# isolated_powerSerial_v2.net
KiCad netlist of a schematic drawn in EAGLE
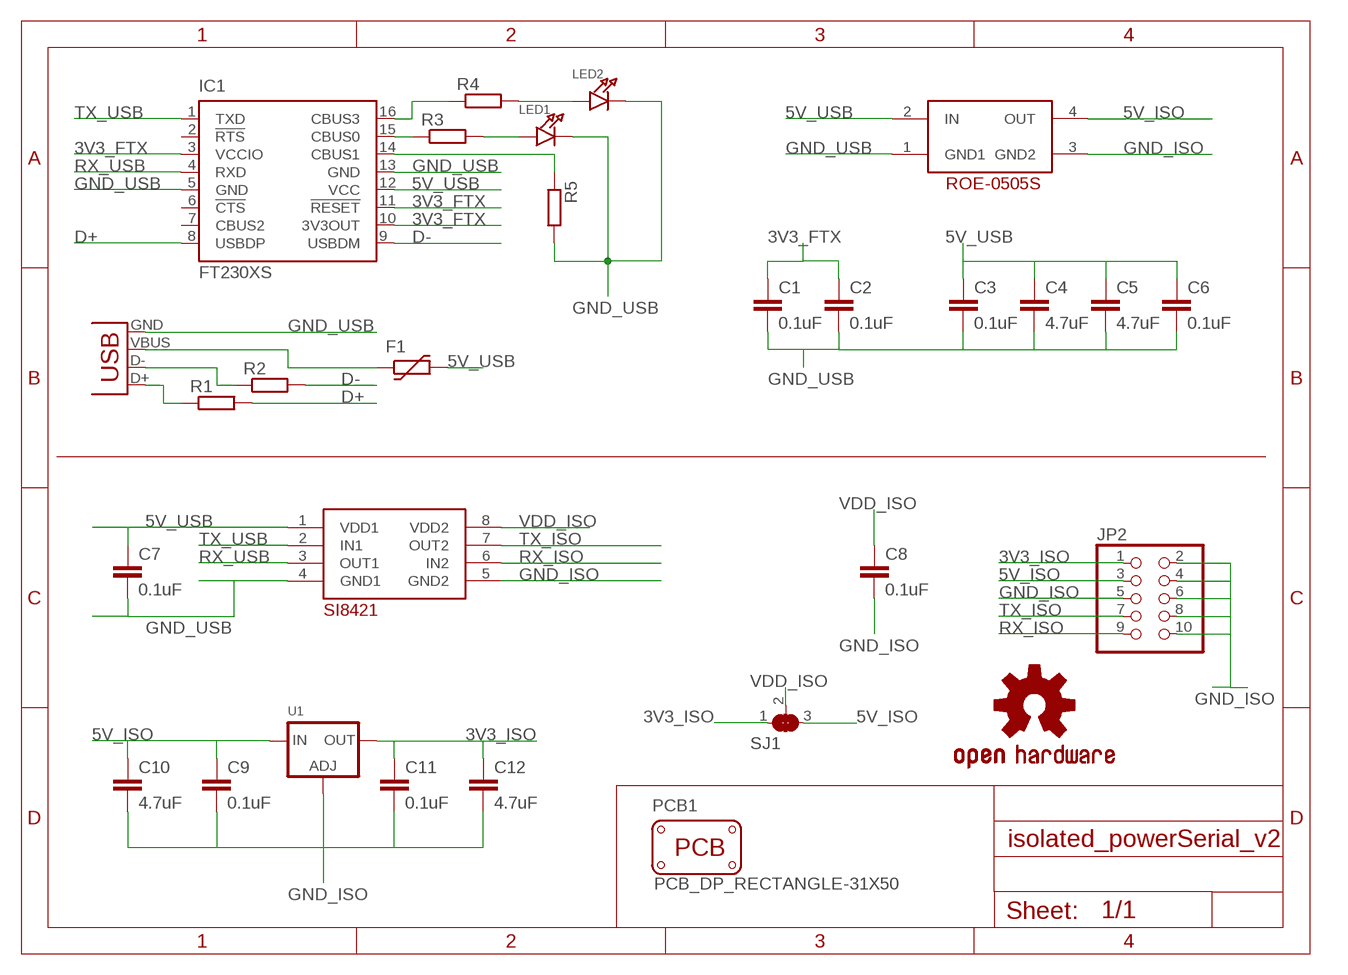
[diagram p0: schematic, sheet 1]

(export (version "E")
  (design (tool "Eeschema 10.0.6"))
  (components
    (comp (ref "C1")
      (value "0.1uF")
      (footprint "eagle-import:C0603")
      (libsource (lib "eagle-import") (part "C-EUC0603"))
    )
    (comp (ref "C2")
      (value "0.1uF")
      (footprint "eagle-import:C0603")
      (libsource (lib "eagle-import") (part "C-EUC0603"))
    )
    (comp (ref "C3")
      (value "0.1uF")
      (footprint "eagle-import:C0603")
      (libsource (lib "eagle-import") (part "C-EUC0603"))
    )
    (comp (ref "C4")
      (value "4.7uF")
      (footprint "eagle-import:C0603")
      (libsource (lib "eagle-import") (part "C-EUC0603"))
    )
    (comp (ref "C5")
      (value "4.7uF")
      (footprint "eagle-import:C0603")
      (libsource (lib "eagle-import") (part "C-EUC0603"))
    )
    (comp (ref "C6")
      (value "0.1uF")
      (footprint "eagle-import:C0603")
      (libsource (lib "eagle-import") (part "C-EUC0603"))
    )
    (comp (ref "C7")
      (value "0.1uF")
      (footprint "eagle-import:C0603")
      (libsource (lib "eagle-import") (part "C-EUC0603"))
    )
    (comp (ref "C8")
      (value "0.1uF")
      (footprint "eagle-import:C0603")
      (libsource (lib "eagle-import") (part "C-EUC0603"))
    )
    (comp (ref "C9")
      (value "0.1uF")
      (footprint "eagle-import:C0603")
      (libsource (lib "eagle-import") (part "C-EUC0603"))
    )
    (comp (ref "C10")
      (value "4.7uF")
      (footprint "eagle-import:C0603")
      (libsource (lib "eagle-import") (part "C-EUC0603"))
    )
    (comp (ref "C11")
      (value "0.1uF")
      (footprint "eagle-import:C0603")
      (libsource (lib "eagle-import") (part "C-EUC0603"))
    )
    (comp (ref "C12")
      (value "4.7uF")
      (footprint "eagle-import:C0603")
      (libsource (lib "eagle-import") (part "C-EUC0603"))
    )
    (comp (ref "F1")
      (value "FUSE_PTC-0805")
      (footprint "eagle-import:PTC0805")
      (libsource (lib "eagle-import") (part "FUSE_PTC-0805"))
    )
    (comp (ref "IC1")
      (value "FT230XS")
      (footprint "eagle-import:SSOP16")
      (libsource (lib "eagle-import") (part "FT230XS"))
    )
    (comp (ref "JP1")
      (value "USB-SMD-NS")
      (footprint "eagle-import:USB-MINIB-NOSTOP")
      (libsource (lib "eagle-import") (part "USB-SMD-NS"))
    )
    (comp (ref "JP2")
      (value "PINHD-2X5")
      (footprint "eagle-import:2X05")
      (libsource (lib "eagle-import") (part "PINHD-2X5"))
    )
    (comp (ref "LED1")
      (value "LED0805")
      (footprint "eagle-import:CHIPLED_0805")
      (libsource (lib "eagle-import") (part "LED0805"))
    )
    (comp (ref "LED2")
      (value "LED0805")
      (footprint "eagle-import:CHIPLED_0805")
      (libsource (lib "eagle-import") (part "LED0805"))
    )
    (comp (ref "LOGO1")
      (value "OSHW-LOGOS")
      (footprint "eagle-import:OSHW-LOGO-S")
      (libsource (lib "eagle-import") (part "OSHW-LOGOS"))
    )
    (comp (ref "PCB1")
      (value "PCB_DP_RECTANGLE-31X50")
      (footprint "eagle-import:DP5031_V1")
      (libsource (lib "eagle-import") (part "PCB_DP_RECTANGLE-31X50"))
    )
    (comp (ref "R1")
      (value "R-EU_R0603")
      (footprint "eagle-import:R0603")
      (libsource (lib "eagle-import") (part "R-EU_R0603"))
    )
    (comp (ref "R2")
      (value "R-EU_R0603")
      (footprint "eagle-import:R0603")
      (libsource (lib "eagle-import") (part "R-EU_R0603"))
    )
    (comp (ref "R3")
      (value "R-EU_R0603")
      (footprint "eagle-import:R0603")
      (libsource (lib "eagle-import") (part "R-EU_R0603"))
    )
    (comp (ref "R4")
      (value "R-EU_R0603")
      (footprint "eagle-import:R0603")
      (libsource (lib "eagle-import") (part "R-EU_R0603"))
    )
    (comp (ref "R5")
      (value "R-EU_R0603")
      (footprint "eagle-import:R0603")
      (libsource (lib "eagle-import") (part "R-EU_R0603"))
    )
    (comp (ref "SJ1")
      (value "SOLDERJUMPER_2WAY0603")
      (footprint "eagle-import:SOLDERJUMPER_2WAY_OPEN_0603")
      (libsource (lib "eagle-import") (part "SOLDERJUMPER_2WAY0603"))
    )
    (comp (ref "U$1")
      (value "IHSAN_RECOM_ROE-0505S")
      (footprint "eagle-import:IHSAN_ROE")
      (libsource (lib "eagle-import") (part "IHSAN_RECOM_ROE-0505S"))
    )
    (comp (ref "U$2")
      (value "IHSAN_SI8421")
      (footprint "eagle-import:SO08")
      (libsource (lib "eagle-import") (part "IHSAN_SI8421"))
    )
    (comp (ref "U1")
      (value "LM1117SOT223-REFLOW")
      (footprint "eagle-import:SOT223-R")
      (libsource (lib "eagle-import") (part "LM1117SOT223-REFLOW"))
    )
  )
  (nets
    (net (code "1") (name "/3V3_FTX") (class "Default")
      (node (ref "C1") (pin "1") (pinfunction "1_1") (pintype "passive"))
      (node (ref "C2") (pin "1") (pinfunction "1_1") (pintype "passive"))
      (node (ref "IC1") (pin "10") (pinfunction "3V3OUT_10") (pintype "output"))
      (node (ref "IC1") (pin "11") (pinfunction "~{RESET}_11") (pintype "input"))
      (node (ref "IC1") (pin "3") (pinfunction "VCCIO_3") (pintype "power_in"))
    )
    (net (code "2") (name "/3V3_ISO") (class "Default")
      (node (ref "C11") (pin "1") (pinfunction "1_1") (pintype "passive"))
      (node (ref "C12") (pin "1") (pinfunction "1_1") (pintype "passive"))
      (node (ref "JP2") (pin "1") (pinfunction "1_1") (pintype "passive"))
      (node (ref "SJ1") (pin "1") (pinfunction "1_1") (pintype "passive"))
      (node (ref "U1") (pin "2") (pinfunction "OUT_2") (pintype "passive"))
    )
    (net (code "3") (name "/5V_ISO") (class "Default")
      (node (ref "C10") (pin "1") (pinfunction "1_1") (pintype "passive"))
      (node (ref "C9") (pin "1") (pinfunction "1_1") (pintype "passive"))
      (node (ref "JP2") (pin "3") (pinfunction "3_3") (pintype "passive"))
      (node (ref "SJ1") (pin "3") (pinfunction "3_3") (pintype "passive"))
      (node (ref "U$1") (pin "4") (pinfunction "OUT_4") (pintype "bidirectional"))
      (node (ref "U1") (pin "3") (pinfunction "IN_3") (pintype "input"))
    )
    (net (code "4") (name "/5V_USB") (class "Default")
      (node (ref "C3") (pin "1") (pinfunction "1_1") (pintype "passive"))
      (node (ref "C4") (pin "1") (pinfunction "1_1") (pintype "passive"))
      (node (ref "C5") (pin "1") (pinfunction "1_1") (pintype "passive"))
      (node (ref "C6") (pin "1") (pinfunction "1_1") (pintype "passive"))
      (node (ref "C7") (pin "1") (pinfunction "1_1") (pintype "passive"))
      (node (ref "F1") (pin "2") (pinfunction "2_2") (pintype "passive"))
      (node (ref "IC1") (pin "12") (pinfunction "VCC_12") (pintype "power_in"))
      (node (ref "U$1") (pin "2") (pinfunction "IN_2") (pintype "bidirectional"))
      (node (ref "U$2") (pin "1") (pinfunction "VDD1_1") (pintype "bidirectional"))
    )
    (net (code "5") (name "/D+") (class "Default")
      (node (ref "IC1") (pin "8") (pinfunction "USBDP_8") (pintype "input"))
      (node (ref "R1") (pin "2") (pinfunction "2_2") (pintype "passive"))
    )
    (net (code "6") (name "/D-") (class "Default")
      (node (ref "IC1") (pin "9") (pinfunction "USBDM_9") (pintype "input"))
      (node (ref "R2") (pin "2") (pinfunction "2_2") (pintype "passive"))
    )
    (net (code "7") (name "/GND_ISO") (class "Default")
      (node (ref "C10") (pin "2") (pinfunction "2_2") (pintype "passive"))
      (node (ref "C11") (pin "2") (pinfunction "2_2") (pintype "passive"))
      (node (ref "C12") (pin "2") (pinfunction "2_2") (pintype "passive"))
      (node (ref "C8") (pin "2") (pinfunction "2_2") (pintype "passive"))
      (node (ref "C9") (pin "2") (pinfunction "2_2") (pintype "passive"))
      (node (ref "JP2") (pin "10") (pinfunction "10_10") (pintype "passive"))
      (node (ref "JP2") (pin "2") (pinfunction "2_2") (pintype "passive"))
      (node (ref "JP2") (pin "4") (pinfunction "4_4") (pintype "passive"))
      (node (ref "JP2") (pin "5") (pinfunction "5_5") (pintype "passive"))
      (node (ref "JP2") (pin "6") (pinfunction "6_6") (pintype "passive"))
      (node (ref "JP2") (pin "8") (pinfunction "8_8") (pintype "passive"))
      (node (ref "U$1") (pin "3") (pinfunction "GND2_3") (pintype "bidirectional"))
      (node (ref "U$2") (pin "5") (pinfunction "GND2_5") (pintype "bidirectional"))
      (node (ref "U1") (pin "1") (pinfunction "ADJ_1") (pintype "input"))
    )
    (net (code "8") (name "/GND_USB") (class "Default")
      (node (ref "C1") (pin "2") (pinfunction "2_2") (pintype "passive"))
      (node (ref "C2") (pin "2") (pinfunction "2_2") (pintype "passive"))
      (node (ref "C3") (pin "2") (pinfunction "2_2") (pintype "passive"))
      (node (ref "C4") (pin "2") (pinfunction "2_2") (pintype "passive"))
      (node (ref "C5") (pin "2") (pinfunction "2_2") (pintype "passive"))
      (node (ref "C6") (pin "2") (pinfunction "2_2") (pintype "passive"))
      (node (ref "C7") (pin "2") (pinfunction "2_2") (pintype "passive"))
      (node (ref "IC1") (pin "13") (pinfunction "GND_13") (pintype "power_in"))
      (node (ref "IC1") (pin "5") (pinfunction "GND_5") (pintype "power_in"))
      (node (ref "JP1") (pin "GND") (pinfunction "GND_GND") (pintype "bidirectional"))
      (node (ref "LED1") (pin "C") (pinfunction "C_C") (pintype "passive"))
      (node (ref "LED2") (pin "C") (pinfunction "C_C") (pintype "passive"))
      (node (ref "R5") (pin "2") (pinfunction "2_2") (pintype "passive"))
      (node (ref "U$1") (pin "1") (pinfunction "GND1_1") (pintype "bidirectional"))
      (node (ref "U$2") (pin "4") (pinfunction "GND1_4") (pintype "bidirectional"))
    )
    (net (code "9") (name "/RX_ISO") (class "Default")
      (node (ref "JP2") (pin "9") (pinfunction "9_9") (pintype "passive"))
      (node (ref "U$2") (pin "6") (pinfunction "IN2_6") (pintype "bidirectional"))
    )
    (net (code "10") (name "/RX_USB") (class "Default")
      (node (ref "IC1") (pin "4") (pinfunction "RXD_4") (pintype "input"))
      (node (ref "U$2") (pin "3") (pinfunction "OUT1_3") (pintype "bidirectional"))
    )
    (net (code "11") (name "/TX_ISO") (class "Default")
      (node (ref "JP2") (pin "7") (pinfunction "7_7") (pintype "passive"))
      (node (ref "U$2") (pin "7") (pinfunction "OUT2_7") (pintype "bidirectional"))
    )
    (net (code "12") (name "/TX_USB") (class "Default")
      (node (ref "IC1") (pin "1") (pinfunction "TXD_1") (pintype "output"))
      (node (ref "U$2") (pin "2") (pinfunction "IN1_2") (pintype "bidirectional"))
    )
    (net (code "13") (name "/VDD_ISO") (class "Default")
      (node (ref "C8") (pin "1") (pinfunction "1_1") (pintype "passive"))
      (node (ref "SJ1") (pin "2") (pinfunction "2_2") (pintype "passive"))
      (node (ref "U$2") (pin "8") (pinfunction "VDD2_8") (pintype "bidirectional"))
    )
    (net (code "14") (name "Net-(F1-Pad1)") (class "Default")
      (node (ref "F1") (pin "1") (pinfunction "1_1") (pintype "passive"))
      (node (ref "JP1") (pin "VBUS") (pinfunction "VBUS_VBUS") (pintype "bidirectional"))
    )
    (net (code "15") (name "Net-(IC1-CBUS0)") (class "Default")
      (node (ref "IC1") (pin "15") (pinfunction "CBUS0_15") (pintype "bidirectional"))
      (node (ref "R3") (pin "1") (pinfunction "1_1") (pintype "passive"))
    )
    (net (code "16") (name "Net-(IC1-CBUS1)") (class "Default")
      (node (ref "IC1") (pin "14") (pinfunction "CBUS1_14") (pintype "bidirectional"))
      (node (ref "R5") (pin "1") (pinfunction "1_1") (pintype "passive"))
    )
    (net (code "17") (name "Net-(IC1-CBUS3)") (class "Default")
      (node (ref "IC1") (pin "16") (pinfunction "CBUS3_16") (pintype "bidirectional"))
      (node (ref "R4") (pin "1") (pinfunction "1_1") (pintype "passive"))
    )
    (net (code "18") (name "Net-(JP1-PadD+)") (class "Default")
      (node (ref "JP1") (pin "D+") (pinfunction "D+_D+") (pintype "bidirectional"))
      (node (ref "R1") (pin "1") (pinfunction "1_1") (pintype "passive"))
    )
    (net (code "19") (name "Net-(JP1-PadD-)") (class "Default")
      (node (ref "JP1") (pin "D-") (pinfunction "D-_D-") (pintype "bidirectional"))
      (node (ref "R2") (pin "1") (pinfunction "1_1") (pintype "passive"))
    )
    (net (code "20") (name "Net-(LED1-PadA)") (class "Default")
      (node (ref "LED1") (pin "A") (pinfunction "A_A") (pintype "passive"))
      (node (ref "R3") (pin "2") (pinfunction "2_2") (pintype "passive"))
    )
    (net (code "21") (name "Net-(LED2-PadA)") (class "Default")
      (node (ref "LED2") (pin "A") (pinfunction "A_A") (pintype "passive"))
      (node (ref "R4") (pin "2") (pinfunction "2_2") (pintype "passive"))
    )
    (net (code "22") (name "unconnected-(IC1-CBUS2-Pad7)") (class "Default")
      (node (ref "IC1") (pin "7") (pinfunction "CBUS2_7") (pintype "bidirectional"))
    )
    (net (code "23") (name "unconnected-(IC1-~{CTS}-Pad6)") (class "Default")
      (node (ref "IC1") (pin "6") (pinfunction "~{CTS}_6") (pintype "input"))
    )
    (net (code "24") (name "unconnected-(IC1-~{RTS}-Pad2)") (class "Default")
      (node (ref "IC1") (pin "2") (pinfunction "~{RTS}_2") (pintype "output"))
    )
  )
)
